# PWR_CTRL.net
KiCad netlist of a schematic drawn in Altium Designer
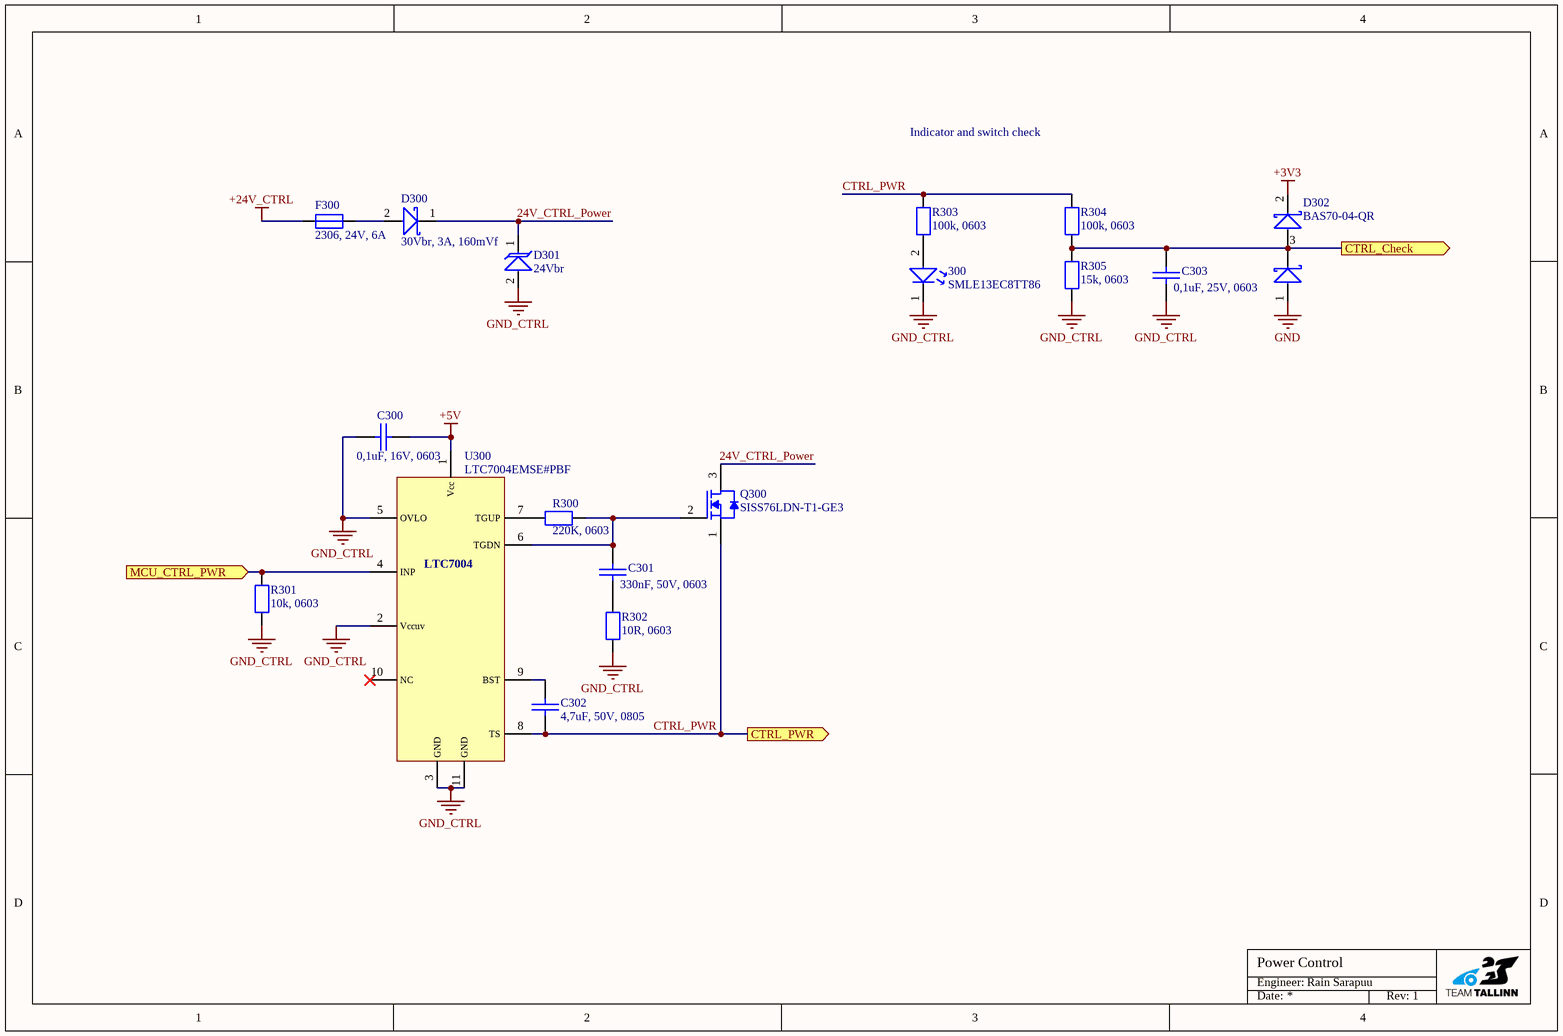
[diagram p0: PWR_CTRL.SchDoc]

(export (version "E")
  (design (tool "Eeschema 10.0.6"))
  (components
    (comp (ref "300")
      (value "SMLE13EC8TT86")
      (footprint "LED [0603] 1608")
      (description "Single Color LED, Green, Colorless Transparent, 1.2mm")
      (libsource (lib "Formula Student Team Tallinn (Estonia)") (part "Diode LED"))
    )
    (comp (ref "C300")
      (value "0,1uF, 16V, 0603")
      (footprint "CAP [0603] 1608")
      (description "Default capacitor part")
      (libsource (lib "Formula Student Team Tallinn (Estonia)") (part "Capacitor"))
    )
    (comp (ref "C301")
      (value "330nF, 50V, 0603")
      (footprint "CAP [0603] 1608")
      (description "Default capacitor part")
      (libsource (lib "Formula Student Team Tallinn (Estonia)") (part "Capacitor"))
    )
    (comp (ref "C302")
      (value "4,7uF, 50V, 0805")
      (footprint "CAP [0805] 2012")
      (description "Default capacitor part")
      (libsource (lib "Formula Student Team Tallinn (Estonia)") (part "Capacitor"))
    )
    (comp (ref "C303")
      (value "0,1uF, 25V, 0603")
      (footprint "CAP [0603] 1608")
      (description "Default capacitor part")
      (libsource (lib "Formula Student Team Tallinn (Estonia)") (part "Capacitor"))
    )
    (comp (ref "D300")
      (value "30Vbr, 3A, 160mVf")
      (footprint "SOD-128")
      (description "Rectifier Diode, Schottky, 1 Phase, 1 Element, 3A, 30V V(RRM), Silicon")
      (fields (field (name "MANUFACTURER PART NUMBER") "PMEG3030EP,115"))
      (libsource (lib "Formula Student Team Tallinn (Estonia)") (part "Diode Shottky"))
    )
    (comp (ref "D301")
      (value "24Vbr")
      (footprint "SOD-128")
      (description "Trans Voltage Suppressor Diode, 600W, 24V V(RWM), Unidirectional, 1 Element, Silicon")
      (fields (field (name "MANUFACTURER PART NUMBER") "VS24VUA1LAMTFTR"))
      (libsource (lib "Formula Student Team Tallinn (Estonia)") (part "Diode TVS"))
    )
    (comp (ref "D302")
      (value "BAS70-04-QR")
      (footprint "SOT23-3")
      (description "Diode Small Signal Schottky 70V 70mA 3-Pin SOT-23 T/R")
      (fields (field (name "MANUFACTURER") "Nexperia"))
      (libsource (lib "Formula Student Team Tallinn (Estonia)") (part "Diode Rail-to-rail"))
    )
    (comp (ref "F300")
      (value "2306, 24V, 6A")
      (footprint "FUSE [1206] 3216")
      (description "Electric Fuse, 6A, 24VDC, 80A (IR), Surface Mount, 1206")
      (fields (field (name "MANUFACTURER PART NUMBER") "SF-1206HIA600M-2"))
      (libsource (lib "Formula Student Team Tallinn (Estonia)") (part "Fuse"))
    )
    (comp (ref "Q300")
      (value "SISS76LDN-T1-GE3")
      (footprint "PowerPAK 1212-8S")
      (description "Power Field-Effect Transistor")
      (fields (field (name "MANUFACTURER") "Vishay"))
      (libsource (lib "Formula Student Team Tallinn (Estonia)") (part "SiSS76LDN"))
    )
    (comp (ref "R300")
      (value "220K, 0603")
      (footprint "RES [0603] 1608")
      (description "Standard resistor part")
      (libsource (lib "Formula Student Team Tallinn (Estonia)") (part "Resistor"))
    )
    (comp (ref "R301")
      (value "10k, 0603")
      (footprint "RES [0603] 1608")
      (description "Standard resistor part")
      (libsource (lib "Formula Student Team Tallinn (Estonia)") (part "Resistor"))
    )
    (comp (ref "R302")
      (value "10R, 0603")
      (footprint "RES [0603] 1608")
      (description "Standard resistor part")
      (libsource (lib "Formula Student Team Tallinn (Estonia)") (part "Resistor"))
    )
    (comp (ref "R303")
      (value "100k, 0603")
      (footprint "RES [0603] 1608")
      (description "Standard resistor part")
      (libsource (lib "Formula Student Team Tallinn (Estonia)") (part "Resistor"))
    )
    (comp (ref "R304")
      (value "100k, 0603")
      (footprint "RES [0603] 1608")
      (description "Standard resistor part")
      (libsource (lib "Formula Student Team Tallinn (Estonia)") (part "Resistor"))
    )
    (comp (ref "R305")
      (value "15k, 0603")
      (footprint "RES [0603] 1608")
      (description "Standard resistor part")
      (libsource (lib "Formula Student Team Tallinn (Estonia)") (part "Resistor"))
    )
    (comp (ref "U300")
      (value "LTC7004EMSE#PBF")
      (footprint "LTC7004EMSE#PBF-Footprint-1")
      (description "Buffer/Inverter Based MOSFET Driver, CMOS, PDSO10")
      (libsource (lib "Formula Student Team Tallinn (Estonia)") (part "LTC7004EMSE#PBF-Symbol-1"))
    )
  )
  (nets
    (net (code "1") (name "+3V3") (class "Default")
      (node (ref "D302") (pin "2") (pinfunction "2_2") (pintype "passive"))
    )
    (net (code "2") (name "+5V") (class "Default")
      (node (ref "C300") (pin "1") (pinfunction "1_1") (pintype "passive"))
      (node (ref "U300") (pin "1") (pinfunction "Vcc_1") (pintype "passive"))
    )
    (net (code "3") (name "+24V_CTRL") (class "Default")
      (node (ref "F300") (pin "2") (pinfunction "2_2") (pintype "passive"))
    )
    (net (code "4") (name "/24V_CTRL_Power") (class "Default")
      (node (ref "D300") (pin "1") (pinfunction "K_1") (pintype "passive"))
      (node (ref "D301") (pin "1") (pinfunction "K_1") (pintype "passive"))
      (node (ref "Q300") (pin "3") (pinfunction "D_3") (pintype "passive"))
    )
    (net (code "5") (name "/CTRL_Check") (class "Default")
      (node (ref "C303") (pin "1") (pinfunction "1_1") (pintype "passive"))
      (node (ref "D302") (pin "3") (pinfunction "3_3") (pintype "passive"))
      (node (ref "R304") (pin "1") (pinfunction "1_1") (pintype "passive"))
      (node (ref "R305") (pin "2") (pinfunction "2_2") (pintype "passive"))
    )
    (net (code "6") (name "/CTRL_PWR") (class "Default")
      (node (ref "C302") (pin "2") (pinfunction "2_2") (pintype "passive"))
      (node (ref "Q300") (pin "1") (pinfunction "S_1") (pintype "passive"))
      (node (ref "R303") (pin "2") (pinfunction "2_2") (pintype "passive"))
      (node (ref "R304") (pin "2") (pinfunction "2_2") (pintype "passive"))
      (node (ref "U300") (pin "8") (pinfunction "TS_8") (pintype "passive"))
    )
    (net (code "7") (name "/MCU_CTRL_PWR") (class "Default")
      (node (ref "R301") (pin "1") (pinfunction "1_1") (pintype "passive"))
      (node (ref "U300") (pin "4") (pinfunction "INP_4") (pintype "passive"))
    )
    (net (code "8") (name "GND") (class "Default")
      (node (ref "D302") (pin "1") (pinfunction "1_1") (pintype "passive"))
    )
    (net (code "9") (name "GND_CTRL") (class "Default")
      (node (ref "300") (pin "1") (pinfunction "1_1") (pintype "passive"))
      (node (ref "C300") (pin "2") (pinfunction "2_2") (pintype "passive"))
      (node (ref "C303") (pin "2") (pinfunction "2_2") (pintype "passive"))
      (node (ref "D301") (pin "2") (pinfunction "A_2") (pintype "passive"))
      (node (ref "R301") (pin "2") (pinfunction "2_2") (pintype "passive"))
      (node (ref "R302") (pin "1") (pinfunction "1_1") (pintype "passive"))
      (node (ref "R305") (pin "1") (pinfunction "1_1") (pintype "passive"))
      (node (ref "U300") (pin "11") (pinfunction "GND_11") (pintype "passive"))
      (node (ref "U300") (pin "2") (pinfunction "Vccuv_2") (pintype "passive"))
      (node (ref "U300") (pin "3") (pinfunction "GND_3") (pintype "passive"))
      (node (ref "U300") (pin "5") (pinfunction "OVLO_5") (pintype "passive"))
    )
    (net (code "10") (name "Net-(300-Pad2)") (class "Default")
      (node (ref "300") (pin "2") (pinfunction "2_2") (pintype "passive"))
      (node (ref "R303") (pin "1") (pinfunction "1_1") (pintype "passive"))
    )
    (net (code "11") (name "Net-(C301-Pad2)") (class "Default")
      (node (ref "C301") (pin "2") (pinfunction "2_2") (pintype "passive"))
      (node (ref "R302") (pin "2") (pinfunction "2_2") (pintype "passive"))
    )
    (net (code "12") (name "Net-(D300-A)") (class "Default")
      (node (ref "D300") (pin "2") (pinfunction "A_2") (pintype "passive"))
      (node (ref "F300") (pin "1") (pinfunction "1_1") (pintype "passive"))
    )
    (net (code "13") (name "Net-(Q300-G)") (class "Default")
      (node (ref "C301") (pin "1") (pinfunction "1_1") (pintype "passive"))
      (node (ref "Q300") (pin "2") (pinfunction "G_2") (pintype "passive"))
      (node (ref "R300") (pin "2") (pinfunction "2_2") (pintype "passive"))
      (node (ref "U300") (pin "6") (pinfunction "TGDN_6") (pintype "passive"))
    )
    (net (code "14") (name "Net-(U300-BST)") (class "Default")
      (node (ref "C302") (pin "1") (pinfunction "1_1") (pintype "passive"))
      (node (ref "U300") (pin "9") (pinfunction "BST_9") (pintype "passive"))
    )
    (net (code "15") (name "Net-(U300-TGUP)") (class "Default")
      (node (ref "R300") (pin "1") (pinfunction "1_1") (pintype "passive"))
      (node (ref "U300") (pin "7") (pinfunction "TGUP_7") (pintype "passive"))
    )
    (net (code "16") (name "unconnected-(U300-NC-Pad10)") (class "Default")
      (node (ref "U300") (pin "10") (pinfunction "NC_10") (pintype "passive+no_connect"))
    )
  )
)
